# Cell_Balancing_Interface.net
KiCad netlist of a schematic drawn in Altium Designer
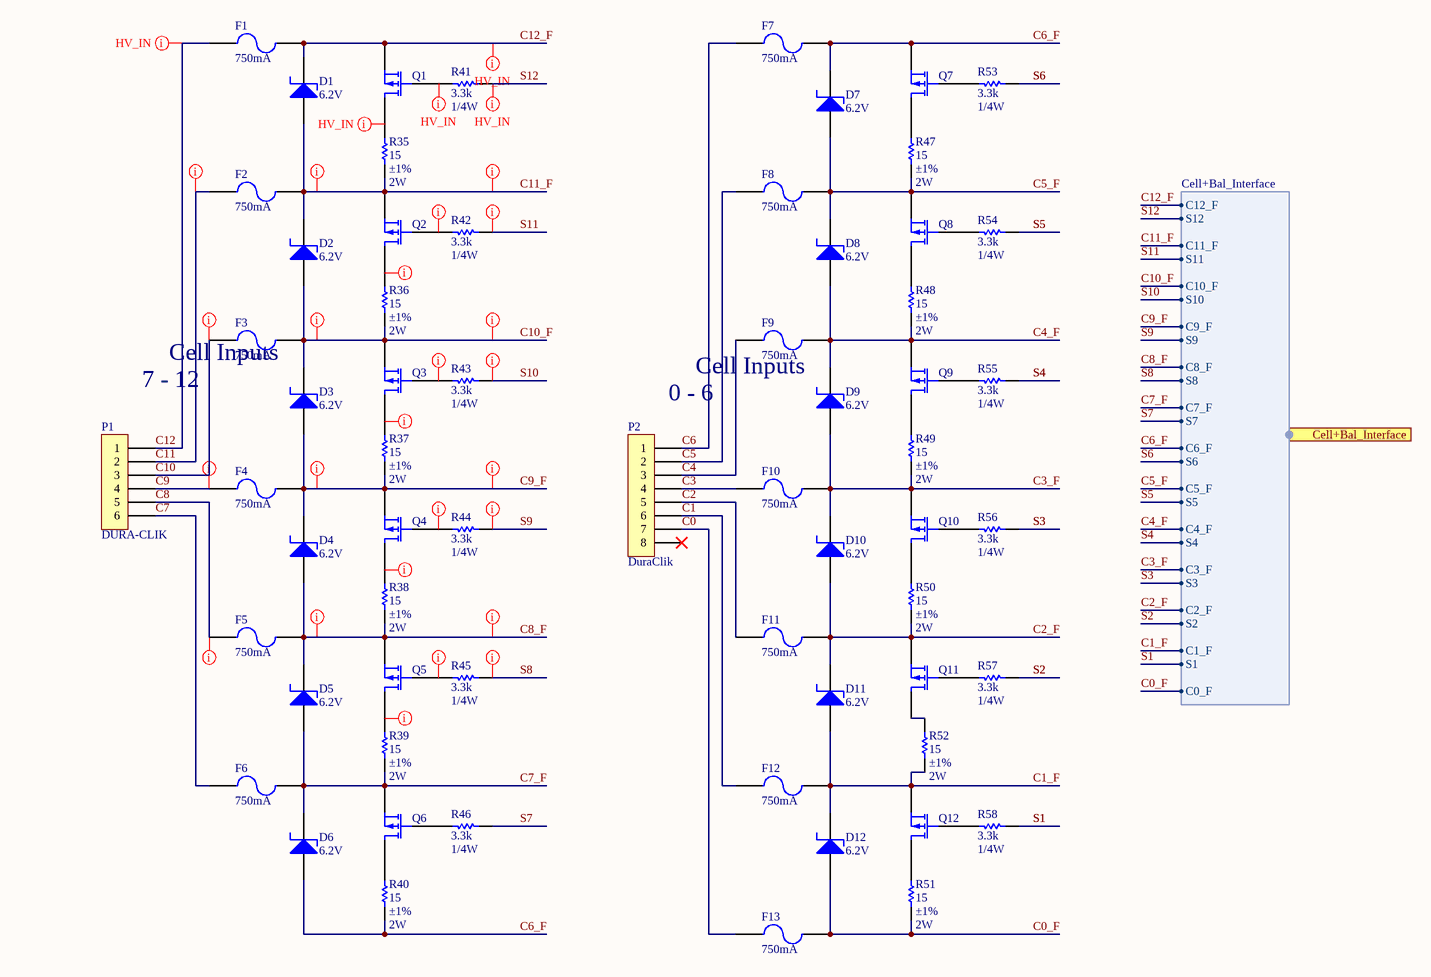
[diagram p0: Cell+Balancing_Interface.SchDoc]

(export (version "E")
  (design (tool "Eeschema 10.0.6"))
  (components
    (comp (ref "D1")
      (value "DIODE ZENER 6.2V 5W DO214AA")
      (footprint "DO-214AA Diode")
      (description "Zener Diode 6.2V 5W ±5% Surface Mount DO-214AA (SMB)")
      (fields (field (name "TOLERANCE") "±5%") (field (name "VOLTAGE - ZENER (NOM)") "6.2V"))
      (libsource (lib "Schematic Diagrams") (part "DIODE ZENER 6.2V 5W DO214AA"))
    )
    (comp (ref "D2")
      (value "DIODE ZENER 6.2V 5W DO214AA")
      (footprint "DO-214AA Diode")
      (description "Zener Diode 6.2V 5W ±5% Surface Mount DO-214AA (SMB)")
      (fields (field (name "TOLERANCE") "±5%") (field (name "VOLTAGE - ZENER (NOM)") "6.2V"))
      (libsource (lib "Schematic Diagrams") (part "DIODE ZENER 6.2V 5W DO214AA"))
    )
    (comp (ref "D3")
      (value "DIODE ZENER 6.2V 5W DO214AA")
      (footprint "DO-214AA Diode")
      (description "Zener Diode 6.2V 5W ±5% Surface Mount DO-214AA (SMB)")
      (fields (field (name "TOLERANCE") "±5%") (field (name "VOLTAGE - ZENER (NOM)") "6.2V"))
      (libsource (lib "Schematic Diagrams") (part "DIODE ZENER 6.2V 5W DO214AA"))
    )
    (comp (ref "D4")
      (value "DIODE ZENER 6.2V 5W DO214AA")
      (footprint "DO-214AA Diode")
      (description "Zener Diode 6.2V 5W ±5% Surface Mount DO-214AA (SMB)")
      (fields (field (name "TOLERANCE") "±5%") (field (name "VOLTAGE - ZENER (NOM)") "6.2V"))
      (libsource (lib "Schematic Diagrams") (part "DIODE ZENER 6.2V 5W DO214AA"))
    )
    (comp (ref "D5")
      (value "DIODE ZENER 6.2V 5W DO214AA")
      (footprint "DO-214AA Diode")
      (description "Zener Diode 6.2V 5W ±5% Surface Mount DO-214AA (SMB)")
      (fields (field (name "TOLERANCE") "±5%") (field (name "VOLTAGE - ZENER (NOM)") "6.2V"))
      (libsource (lib "Schematic Diagrams") (part "DIODE ZENER 6.2V 5W DO214AA"))
    )
    (comp (ref "D6")
      (value "DIODE ZENER 6.2V 5W DO214AA")
      (footprint "DO-214AA Diode")
      (description "Zener Diode 6.2V 5W ±5% Surface Mount DO-214AA (SMB)")
      (fields (field (name "TOLERANCE") "±5%") (field (name "VOLTAGE - ZENER (NOM)") "6.2V"))
      (libsource (lib "Schematic Diagrams") (part "DIODE ZENER 6.2V 5W DO214AA"))
    )
    (comp (ref "D7")
      (value "DIODE ZENER 6.2V 5W DO214AA")
      (footprint "DO-214AA Diode")
      (description "Zener Diode 6.2V 5W ±5% Surface Mount DO-214AA (SMB)")
      (fields (field (name "TOLERANCE") "±5%") (field (name "VOLTAGE - ZENER (NOM)") "6.2V"))
      (libsource (lib "Schematic Diagrams") (part "DIODE ZENER 6.2V 5W DO214AA"))
    )
    (comp (ref "D8")
      (value "DIODE ZENER 6.2V 5W DO214AA")
      (footprint "DO-214AA Diode")
      (description "Zener Diode 6.2V 5W ±5% Surface Mount DO-214AA (SMB)")
      (fields (field (name "TOLERANCE") "±5%") (field (name "VOLTAGE - ZENER (NOM)") "6.2V"))
      (libsource (lib "Schematic Diagrams") (part "DIODE ZENER 6.2V 5W DO214AA"))
    )
    (comp (ref "D9")
      (value "DIODE ZENER 6.2V 5W DO214AA")
      (footprint "DO-214AA Diode")
      (description "Zener Diode 6.2V 5W ±5% Surface Mount DO-214AA (SMB)")
      (fields (field (name "TOLERANCE") "±5%") (field (name "VOLTAGE - ZENER (NOM)") "6.2V"))
      (libsource (lib "Schematic Diagrams") (part "DIODE ZENER 6.2V 5W DO214AA"))
    )
    (comp (ref "D10")
      (value "DIODE ZENER 6.2V 5W DO214AA")
      (footprint "DO-214AA Diode")
      (description "Zener Diode 6.2V 5W ±5% Surface Mount DO-214AA (SMB)")
      (fields (field (name "TOLERANCE") "±5%") (field (name "VOLTAGE - ZENER (NOM)") "6.2V"))
      (libsource (lib "Schematic Diagrams") (part "DIODE ZENER 6.2V 5W DO214AA"))
    )
    (comp (ref "D11")
      (value "DIODE ZENER 6.2V 5W DO214AA")
      (footprint "DO-214AA Diode")
      (description "Zener Diode 6.2V 5W ±5% Surface Mount DO-214AA (SMB)")
      (fields (field (name "TOLERANCE") "±5%") (field (name "VOLTAGE - ZENER (NOM)") "6.2V"))
      (libsource (lib "Schematic Diagrams") (part "DIODE ZENER 6.2V 5W DO214AA"))
    )
    (comp (ref "D12")
      (value "DIODE ZENER 6.2V 5W DO214AA")
      (footprint "DO-214AA Diode")
      (description "Zener Diode 6.2V 5W ±5% Surface Mount DO-214AA (SMB)")
      (fields (field (name "TOLERANCE") "±5%") (field (name "VOLTAGE - ZENER (NOM)") "6.2V"))
      (libsource (lib "Schematic Diagrams") (part "DIODE ZENER 6.2V 5W DO214AA"))
    )
    (comp (ref "F1")
      (value "FUSE SMT 750MA")
      (footprint "RES, 0603")
      (description "Board Mount Fuse 750MA 32VAC 63VDC")
      (fields (field (name "CURRENT RATING") "750mA"))
      (libsource (lib "Schematic Diagrams") (part "FUSE SMT 750MA"))
    )
    (comp (ref "F2")
      (value "FUSE SMT 750MA")
      (footprint "RES, 0603")
      (description "Board Mount Fuse 750MA 32VAC 63VDC")
      (fields (field (name "CURRENT RATING") "750mA"))
      (libsource (lib "Schematic Diagrams") (part "FUSE SMT 750MA"))
    )
    (comp (ref "F3")
      (value "FUSE SMT 750MA")
      (footprint "RES, 0603")
      (description "Board Mount Fuse 750MA 32VAC 63VDC")
      (fields (field (name "CURRENT RATING") "750mA"))
      (libsource (lib "Schematic Diagrams") (part "FUSE SMT 750MA"))
    )
    (comp (ref "F4")
      (value "FUSE SMT 750MA")
      (footprint "RES, 0603")
      (description "Board Mount Fuse 750MA 32VAC 63VDC")
      (fields (field (name "CURRENT RATING") "750mA"))
      (libsource (lib "Schematic Diagrams") (part "FUSE SMT 750MA"))
    )
    (comp (ref "F5")
      (value "FUSE SMT 750MA")
      (footprint "RES, 0603")
      (description "Board Mount Fuse 750MA 32VAC 63VDC")
      (fields (field (name "CURRENT RATING") "750mA"))
      (libsource (lib "Schematic Diagrams") (part "FUSE SMT 750MA"))
    )
    (comp (ref "F6")
      (value "FUSE SMT 750MA")
      (footprint "RES, 0603")
      (description "Board Mount Fuse 750MA 32VAC 63VDC")
      (fields (field (name "CURRENT RATING") "750mA"))
      (libsource (lib "Schematic Diagrams") (part "FUSE SMT 750MA"))
    )
    (comp (ref "F7")
      (value "FUSE SMT 750MA")
      (footprint "RES, 0603")
      (description "Board Mount Fuse 750MA 32VAC 63VDC")
      (fields (field (name "CURRENT RATING") "750mA"))
      (libsource (lib "Schematic Diagrams") (part "FUSE SMT 750MA"))
    )
    (comp (ref "F8")
      (value "FUSE SMT 750MA")
      (footprint "RES, 0603")
      (description "Board Mount Fuse 750MA 32VAC 63VDC")
      (fields (field (name "CURRENT RATING") "750mA"))
      (libsource (lib "Schematic Diagrams") (part "FUSE SMT 750MA"))
    )
    (comp (ref "F9")
      (value "FUSE SMT 750MA")
      (footprint "RES, 0603")
      (description "Board Mount Fuse 750MA 32VAC 63VDC")
      (fields (field (name "CURRENT RATING") "750mA"))
      (libsource (lib "Schematic Diagrams") (part "FUSE SMT 750MA"))
    )
    (comp (ref "F10")
      (value "FUSE SMT 750MA")
      (footprint "RES, 0603")
      (description "Board Mount Fuse 750MA 32VAC 63VDC")
      (fields (field (name "CURRENT RATING") "750mA"))
      (libsource (lib "Schematic Diagrams") (part "FUSE SMT 750MA"))
    )
    (comp (ref "F11")
      (value "FUSE SMT 750MA")
      (footprint "RES, 0603")
      (description "Board Mount Fuse 750MA 32VAC 63VDC")
      (fields (field (name "CURRENT RATING") "750mA"))
      (libsource (lib "Schematic Diagrams") (part "FUSE SMT 750MA"))
    )
    (comp (ref "F12")
      (value "FUSE SMT 750MA")
      (footprint "RES, 0603")
      (description "Board Mount Fuse 750MA 32VAC 63VDC")
      (fields (field (name "CURRENT RATING") "750mA"))
      (libsource (lib "Schematic Diagrams") (part "FUSE SMT 750MA"))
    )
    (comp (ref "F13")
      (value "FUSE SMT 750MA")
      (footprint "RES, 0603")
      (description "Board Mount Fuse 750MA 32VAC 63VDC")
      (fields (field (name "CURRENT RATING") "750mA"))
      (libsource (lib "Schematic Diagrams") (part "FUSE SMT 750MA"))
    )
    (comp (ref "P1")
      (value "DURA-CLIK")
      (footprint "CONN, 6POS DURA-CLIK VERT")
      (description "6 Positions Header, Shrouded Connector 0.079\" (2.00mm) Surface Mount, Vertical Tin")
      (fields (field (name "MANUFACTURER") "Molex") (field (name "MANUFACTURER PART NUMBER") "5600200820"))
      (libsource (lib "Schematic Diagrams") (part "CONN 6POS DURA-CLIK 0.079{dblquote}"))
    )
    (comp (ref "P2")
      (value "CONN 8POS DURA-CLIK 0.079\"")
      (footprint "CONN, 8POS Dura-Clik")
      (description "8 Positions Header Connector 0.079\" (2.00mm) Surface Mount Tin")
      (fields (field (name "SERIES") "DuraClik"))
      (libsource (lib "Schematic Diagrams") (part "CONN 8POS DURA-CLIK 0.079{dblquote}"))
    )
    (comp (ref "Q1")
      (value "MOSFET P-CH 16V 2.5A X2-DFN2015")
      (footprint "DFN86P197X40-3N")
      (description "P-Channel 16V 2.5A (Ta) 650mW (Ta) Surface Mount X2-DFN2015-3")
      (libsource (lib "Schematic Diagrams") (part "MOSFET P-CH 16V 2.5A X2-DFN2015"))
    )
    (comp (ref "Q2")
      (value "MOSFET P-CH 16V 2.5A X2-DFN2015")
      (footprint "DFN86P197X40-3N")
      (description "P-Channel 16V 2.5A (Ta) 650mW (Ta) Surface Mount X2-DFN2015-3")
      (libsource (lib "Schematic Diagrams") (part "MOSFET P-CH 16V 2.5A X2-DFN2015"))
    )
    (comp (ref "Q3")
      (value "MOSFET P-CH 16V 2.5A X2-DFN2015")
      (footprint "DFN86P197X40-3N")
      (description "P-Channel 16V 2.5A (Ta) 650mW (Ta) Surface Mount X2-DFN2015-3")
      (libsource (lib "Schematic Diagrams") (part "MOSFET P-CH 16V 2.5A X2-DFN2015"))
    )
    (comp (ref "Q4")
      (value "MOSFET P-CH 16V 2.5A X2-DFN2015")
      (footprint "DFN86P197X40-3N")
      (description "P-Channel 16V 2.5A (Ta) 650mW (Ta) Surface Mount X2-DFN2015-3")
      (libsource (lib "Schematic Diagrams") (part "MOSFET P-CH 16V 2.5A X2-DFN2015"))
    )
    (comp (ref "Q5")
      (value "MOSFET P-CH 16V 2.5A X2-DFN2015")
      (footprint "DFN86P197X40-3N")
      (description "P-Channel 16V 2.5A (Ta) 650mW (Ta) Surface Mount X2-DFN2015-3")
      (libsource (lib "Schematic Diagrams") (part "MOSFET P-CH 16V 2.5A X2-DFN2015"))
    )
    (comp (ref "Q6")
      (value "MOSFET P-CH 16V 2.5A X2-DFN2015")
      (footprint "DFN86P197X40-3N")
      (description "P-Channel 16V 2.5A (Ta) 650mW (Ta) Surface Mount X2-DFN2015-3")
      (libsource (lib "Schematic Diagrams") (part "MOSFET P-CH 16V 2.5A X2-DFN2015"))
    )
    (comp (ref "Q7")
      (value "MOSFET P-CH 16V 2.5A X2-DFN2015")
      (footprint "DFN86P197X40-3N")
      (description "P-Channel 16V 2.5A (Ta) 650mW (Ta) Surface Mount X2-DFN2015-3")
      (libsource (lib "Schematic Diagrams") (part "MOSFET P-CH 16V 2.5A X2-DFN2015"))
    )
    (comp (ref "Q8")
      (value "MOSFET P-CH 16V 2.5A X2-DFN2015")
      (footprint "DFN86P197X40-3N")
      (description "P-Channel 16V 2.5A (Ta) 650mW (Ta) Surface Mount X2-DFN2015-3")
      (libsource (lib "Schematic Diagrams") (part "MOSFET P-CH 16V 2.5A X2-DFN2015"))
    )
    (comp (ref "Q9")
      (value "MOSFET P-CH 16V 2.5A X2-DFN2015")
      (footprint "DFN86P197X40-3N")
      (description "P-Channel 16V 2.5A (Ta) 650mW (Ta) Surface Mount X2-DFN2015-3")
      (libsource (lib "Schematic Diagrams") (part "MOSFET P-CH 16V 2.5A X2-DFN2015"))
    )
    (comp (ref "Q10")
      (value "MOSFET P-CH 16V 2.5A X2-DFN2015")
      (footprint "DFN86P197X40-3N")
      (description "P-Channel 16V 2.5A (Ta) 650mW (Ta) Surface Mount X2-DFN2015-3")
      (libsource (lib "Schematic Diagrams") (part "MOSFET P-CH 16V 2.5A X2-DFN2015"))
    )
    (comp (ref "Q11")
      (value "MOSFET P-CH 16V 2.5A X2-DFN2015")
      (footprint "DFN86P197X40-3N")
      (description "P-Channel 16V 2.5A (Ta) 650mW (Ta) Surface Mount X2-DFN2015-3")
      (libsource (lib "Schematic Diagrams") (part "MOSFET P-CH 16V 2.5A X2-DFN2015"))
    )
    (comp (ref "Q12")
      (value "MOSFET P-CH 16V 2.5A X2-DFN2015")
      (footprint "DFN86P197X40-3N")
      (description "P-Channel 16V 2.5A (Ta) 650mW (Ta) Surface Mount X2-DFN2015-3")
      (libsource (lib "Schematic Diagrams") (part "MOSFET P-CH 16V 2.5A X2-DFN2015"))
    )
    (comp (ref "R35")
      (value "RES 15 OHM 1% 2W 2512")
      (footprint "RES2512")
      (description "15 Ohm ±1% 2W Chip Resistor 2512 (6432 Metric) Thick Film")
      (fields (field (name "RESISTANCE") "15") (field (name "TOLERANCE") "±1%") (field (name "POWER") "2W"))
      (libsource (lib "Schematic Diagrams") (part "RES 15 OHM 1% 2W 2512"))
    )
    (comp (ref "R36")
      (value "RES 15 OHM 1% 2W 2512")
      (footprint "RES2512")
      (description "15 Ohm ±1% 2W Chip Resistor 2512 (6432 Metric) Thick Film")
      (fields (field (name "RESISTANCE") "15") (field (name "TOLERANCE") "±1%") (field (name "POWER") "2W"))
      (libsource (lib "Schematic Diagrams") (part "RES 15 OHM 1% 2W 2512"))
    )
    (comp (ref "R37")
      (value "RES 15 OHM 1% 2W 2512")
      (footprint "RES2512")
      (description "15 Ohm ±1% 2W Chip Resistor 2512 (6432 Metric) Thick Film")
      (fields (field (name "RESISTANCE") "15") (field (name "TOLERANCE") "±1%") (field (name "POWER") "2W"))
      (libsource (lib "Schematic Diagrams") (part "RES 15 OHM 1% 2W 2512"))
    )
    (comp (ref "R38")
      (value "RES 15 OHM 1% 2W 2512")
      (footprint "RES2512")
      (description "15 Ohm ±1% 2W Chip Resistor 2512 (6432 Metric) Thick Film")
      (fields (field (name "RESISTANCE") "15") (field (name "TOLERANCE") "±1%") (field (name "POWER") "2W"))
      (libsource (lib "Schematic Diagrams") (part "RES 15 OHM 1% 2W 2512"))
    )
    (comp (ref "R39")
      (value "RES 15 OHM 1% 2W 2512")
      (footprint "RES2512")
      (description "15 Ohm ±1% 2W Chip Resistor 2512 (6432 Metric) Thick Film")
      (fields (field (name "RESISTANCE") "15") (field (name "TOLERANCE") "±1%") (field (name "POWER") "2W"))
      (libsource (lib "Schematic Diagrams") (part "RES 15 OHM 1% 2W 2512"))
    )
    (comp (ref "R40")
      (value "RES 15 OHM 1% 2W 2512")
      (footprint "RES2512")
      (description "15 Ohm ±1% 2W Chip Resistor 2512 (6432 Metric) Thick Film")
      (fields (field (name "RESISTANCE") "15") (field (name "TOLERANCE") "±1%") (field (name "POWER") "2W"))
      (libsource (lib "Schematic Diagrams") (part "RES 15 OHM 1% 2W 2512"))
    )
    (comp (ref "R41")
      (value "RES 3.3K OHM 1% 1/4W 0603")
      (footprint "RES, 0603")
      (fields
        (field (name "TOLERANCE") "±1%")
        (field (name "RESISTANCE") "3.3k")
        (field (name "POWER") "1/4W")
      )
      (libsource (lib "Schematic Diagrams") (part "RES 3.3K OHM 1% 1/4W 0603"))
    )
    (comp (ref "R42")
      (value "RES 3.3K OHM 1% 1/4W 0603")
      (footprint "RES, 0603")
      (fields
        (field (name "TOLERANCE") "±1%")
        (field (name "RESISTANCE") "3.3k")
        (field (name "POWER") "1/4W")
      )
      (libsource (lib "Schematic Diagrams") (part "RES 3.3K OHM 1% 1/4W 0603"))
    )
    (comp (ref "R43")
      (value "RES 3.3K OHM 1% 1/4W 0603")
      (footprint "RES, 0603")
      (fields
        (field (name "TOLERANCE") "±1%")
        (field (name "RESISTANCE") "3.3k")
        (field (name "POWER") "1/4W")
      )
      (libsource (lib "Schematic Diagrams") (part "RES 3.3K OHM 1% 1/4W 0603"))
    )
    (comp (ref "R44")
      (value "RES 3.3K OHM 1% 1/4W 0603")
      (footprint "RES, 0603")
      (fields
        (field (name "TOLERANCE") "±1%")
        (field (name "RESISTANCE") "3.3k")
        (field (name "POWER") "1/4W")
      )
      (libsource (lib "Schematic Diagrams") (part "RES 3.3K OHM 1% 1/4W 0603"))
    )
    (comp (ref "R45")
      (value "RES 3.3K OHM 1% 1/4W 0603")
      (footprint "RES, 0603")
      (fields
        (field (name "TOLERANCE") "±1%")
        (field (name "RESISTANCE") "3.3k")
        (field (name "POWER") "1/4W")
      )
      (libsource (lib "Schematic Diagrams") (part "RES 3.3K OHM 1% 1/4W 0603"))
    )
    (comp (ref "R46")
      (value "RES 3.3K OHM 1% 1/4W 0603")
      (footprint "RES, 0603")
      (fields
        (field (name "TOLERANCE") "±1%")
        (field (name "RESISTANCE") "3.3k")
        (field (name "POWER") "1/4W")
      )
      (libsource (lib "Schematic Diagrams") (part "RES 3.3K OHM 1% 1/4W 0603"))
    )
    (comp (ref "R47")
      (value "RES 15 OHM 1% 2W 2512")
      (footprint "RES2512")
      (description "15 Ohm ±1% 2W Chip Resistor 2512 (6432 Metric) Thick Film")
      (fields (field (name "RESISTANCE") "15") (field (name "TOLERANCE") "±1%") (field (name "POWER") "2W"))
      (libsource (lib "Schematic Diagrams") (part "RES 15 OHM 1% 2W 2512"))
    )
    (comp (ref "R48")
      (value "RES 15 OHM 1% 2W 2512")
      (footprint "RES2512")
      (description "15 Ohm ±1% 2W Chip Resistor 2512 (6432 Metric) Thick Film")
      (fields (field (name "RESISTANCE") "15") (field (name "TOLERANCE") "±1%") (field (name "POWER") "2W"))
      (libsource (lib "Schematic Diagrams") (part "RES 15 OHM 1% 2W 2512"))
    )
    (comp (ref "R49")
      (value "RES 15 OHM 1% 2W 2512")
      (footprint "RES2512")
      (description "15 Ohm ±1% 2W Chip Resistor 2512 (6432 Metric) Thick Film")
      (fields (field (name "RESISTANCE") "15") (field (name "TOLERANCE") "±1%") (field (name "POWER") "2W"))
      (libsource (lib "Schematic Diagrams") (part "RES 15 OHM 1% 2W 2512"))
    )
    (comp (ref "R50")
      (value "RES 15 OHM 1% 2W 2512")
      (footprint "RES2512")
      (description "15 Ohm ±1% 2W Chip Resistor 2512 (6432 Metric) Thick Film")
      (fields (field (name "RESISTANCE") "15") (field (name "TOLERANCE") "±1%") (field (name "POWER") "2W"))
      (libsource (lib "Schematic Diagrams") (part "RES 15 OHM 1% 2W 2512"))
    )
    (comp (ref "R51")
      (value "RES 15 OHM 1% 2W 2512")
      (footprint "RES2512")
      (description "15 Ohm ±1% 2W Chip Resistor 2512 (6432 Metric) Thick Film")
      (fields (field (name "RESISTANCE") "15") (field (name "TOLERANCE") "±1%") (field (name "POWER") "2W"))
      (libsource (lib "Schematic Diagrams") (part "RES 15 OHM 1% 2W 2512"))
    )
    (comp (ref "R52")
      (value "RES 15 OHM 1% 2W 2512")
      (footprint "RES2512")
      (description "15 Ohm ±1% 2W Chip Resistor 2512 (6432 Metric) Thick Film")
      (fields (field (name "RESISTANCE") "15") (field (name "TOLERANCE") "±1%") (field (name "POWER") "2W"))
      (libsource (lib "Schematic Diagrams") (part "RES 15 OHM 1% 2W 2512"))
    )
    (comp (ref "R53")
      (value "RES 3.3K OHM 1% 1/4W 0603")
      (footprint "RES, 0603")
      (fields
        (field (name "TOLERANCE") "±1%")
        (field (name "RESISTANCE") "3.3k")
        (field (name "POWER") "1/4W")
      )
      (libsource (lib "Schematic Diagrams") (part "RES 3.3K OHM 1% 1/4W 0603"))
    )
    (comp (ref "R54")
      (value "RES 3.3K OHM 1% 1/4W 0603")
      (footprint "RES, 0603")
      (fields
        (field (name "TOLERANCE") "±1%")
        (field (name "RESISTANCE") "3.3k")
        (field (name "POWER") "1/4W")
      )
      (libsource (lib "Schematic Diagrams") (part "RES 3.3K OHM 1% 1/4W 0603"))
    )
    (comp (ref "R55")
      (value "RES 3.3K OHM 1% 1/4W 0603")
      (footprint "RES, 0603")
      (fields
        (field (name "TOLERANCE") "±1%")
        (field (name "RESISTANCE") "3.3k")
        (field (name "POWER") "1/4W")
      )
      (libsource (lib "Schematic Diagrams") (part "RES 3.3K OHM 1% 1/4W 0603"))
    )
    (comp (ref "R56")
      (value "RES 3.3K OHM 1% 1/4W 0603")
      (footprint "RES, 0603")
      (fields
        (field (name "TOLERANCE") "±1%")
        (field (name "RESISTANCE") "3.3k")
        (field (name "POWER") "1/4W")
      )
      (libsource (lib "Schematic Diagrams") (part "RES 3.3K OHM 1% 1/4W 0603"))
    )
    (comp (ref "R57")
      (value "RES 3.3K OHM 1% 1/4W 0603")
      (footprint "RES, 0603")
      (fields
        (field (name "TOLERANCE") "±1%")
        (field (name "RESISTANCE") "3.3k")
        (field (name "POWER") "1/4W")
      )
      (libsource (lib "Schematic Diagrams") (part "RES 3.3K OHM 1% 1/4W 0603"))
    )
    (comp (ref "R58")
      (value "RES 3.3K OHM 1% 1/4W 0603")
      (footprint "RES, 0603")
      (fields
        (field (name "TOLERANCE") "±1%")
        (field (name "RESISTANCE") "3.3k")
        (field (name "POWER") "1/4W")
      )
      (libsource (lib "Schematic Diagrams") (part "RES 3.3K OHM 1% 1/4W 0603"))
    )
  )
  (nets
    (net (code "2") (name "/C0") (class "Default")
      (node (ref "F13") (pin "1") (pinfunction "1_1") (pintype "passive"))
      (node (ref "P2") (pin "7") (pinfunction "7_7") (pintype "passive"))
    )
    (net (code "3") (name "/C0_F") (class "Default")
      (node (ref "D12") (pin "1") (pinfunction "A_1") (pintype "passive"))
      (node (ref "F13") (pin "2") (pinfunction "2_2") (pintype "passive"))
      (node (ref "R51") (pin "1") (pinfunction "1_1") (pintype "passive"))
    )
    (net (code "4") (name "/C1") (class "Default")
      (node (ref "F12") (pin "1") (pinfunction "1_1") (pintype "passive"))
      (node (ref "P2") (pin "6") (pinfunction "6_6") (pintype "passive"))
    )
    (net (code "5") (name "/C1_F") (class "Default")
      (node (ref "D11") (pin "1") (pinfunction "A_1") (pintype "passive"))
      (node (ref "D12") (pin "2") (pinfunction "K_2") (pintype "passive"))
      (node (ref "F12") (pin "2") (pinfunction "2_2") (pintype "passive"))
      (node (ref "Q12") (pin "2") (pinfunction "S_2") (pintype "passive"))
      (node (ref "R52") (pin "1") (pinfunction "1_1") (pintype "passive"))
    )
    (net (code "6") (name "/C2") (class "Default")
      (node (ref "F11") (pin "1") (pinfunction "1_1") (pintype "passive"))
      (node (ref "P2") (pin "5") (pinfunction "5_5") (pintype "passive"))
    )
    (net (code "7") (name "/C2_F") (class "Default")
      (node (ref "D10") (pin "1") (pinfunction "A_1") (pintype "passive"))
      (node (ref "D11") (pin "2") (pinfunction "K_2") (pintype "passive"))
      (node (ref "F11") (pin "2") (pinfunction "2_2") (pintype "passive"))
      (node (ref "Q11") (pin "2") (pinfunction "S_2") (pintype "passive"))
      (node (ref "R50") (pin "1") (pinfunction "1_1") (pintype "passive"))
    )
    (net (code "8") (name "/C3") (class "Default")
      (node (ref "F10") (pin "1") (pinfunction "1_1") (pintype "passive"))
      (node (ref "P2") (pin "4") (pinfunction "4_4") (pintype "passive"))
    )
    (net (code "9") (name "/C3_F") (class "Default")
      (node (ref "D10") (pin "2") (pinfunction "K_2") (pintype "passive"))
      (node (ref "D9") (pin "1") (pinfunction "A_1") (pintype "passive"))
      (node (ref "F10") (pin "2") (pinfunction "2_2") (pintype "passive"))
      (node (ref "Q10") (pin "2") (pinfunction "S_2") (pintype "passive"))
      (node (ref "R49") (pin "1") (pinfunction "1_1") (pintype "passive"))
    )
    (net (code "10") (name "/C4") (class "Default")
      (node (ref "F9") (pin "1") (pinfunction "1_1") (pintype "passive"))
      (node (ref "P2") (pin "3") (pinfunction "3_3") (pintype "passive"))
    )
    (net (code "11") (name "/C4_F") (class "Default")
      (node (ref "D8") (pin "1") (pinfunction "A_1") (pintype "passive"))
      (node (ref "D9") (pin "2") (pinfunction "K_2") (pintype "passive"))
      (node (ref "F9") (pin "2") (pinfunction "2_2") (pintype "passive"))
      (node (ref "Q9") (pin "2") (pinfunction "S_2") (pintype "passive"))
      (node (ref "R48") (pin "1") (pinfunction "1_1") (pintype "passive"))
    )
    (net (code "12") (name "/C5") (class "Default")
      (node (ref "F8") (pin "1") (pinfunction "1_1") (pintype "passive"))
      (node (ref "P2") (pin "2") (pinfunction "2_2") (pintype "passive"))
    )
    (net (code "13") (name "/C5_F") (class "Default")
      (node (ref "D7") (pin "1") (pinfunction "A_1") (pintype "passive"))
      (node (ref "D8") (pin "2") (pinfunction "K_2") (pintype "passive"))
      (node (ref "F8") (pin "2") (pinfunction "2_2") (pintype "passive"))
      (node (ref "Q8") (pin "2") (pinfunction "S_2") (pintype "passive"))
      (node (ref "R47") (pin "1") (pinfunction "1_1") (pintype "passive"))
    )
    (net (code "14") (name "/C6") (class "Default")
      (node (ref "F7") (pin "1") (pinfunction "1_1") (pintype "passive"))
      (node (ref "P2") (pin "1") (pinfunction "1_1") (pintype "passive"))
    )
    (net (code "15") (name "/C6_F") (class "Default")
      (node (ref "D6") (pin "1") (pinfunction "A_1") (pintype "passive"))
      (node (ref "D7") (pin "2") (pinfunction "K_2") (pintype "passive"))
      (node (ref "F7") (pin "2") (pinfunction "2_2") (pintype "passive"))
      (node (ref "Q7") (pin "2") (pinfunction "S_2") (pintype "passive"))
      (node (ref "R40") (pin "1") (pinfunction "1_1") (pintype "passive"))
    )
    (net (code "16") (name "/C7") (class "Default")
      (node (ref "F6") (pin "1") (pinfunction "1_1") (pintype "passive"))
      (node (ref "P1") (pin "6") (pinfunction "6_6") (pintype "passive"))
    )
    (net (code "17") (name "/C7_F") (class "Default")
      (node (ref "D5") (pin "1") (pinfunction "A_1") (pintype "passive"))
      (node (ref "D6") (pin "2") (pinfunction "K_2") (pintype "passive"))
      (node (ref "F6") (pin "2") (pinfunction "2_2") (pintype "passive"))
      (node (ref "Q6") (pin "2") (pinfunction "S_2") (pintype "passive"))
      (node (ref "R39") (pin "1") (pinfunction "1_1") (pintype "passive"))
    )
    (net (code "18") (name "/C8") (class "Default")
      (node (ref "F5") (pin "1") (pinfunction "1_1") (pintype "passive"))
      (node (ref "P1") (pin "5") (pinfunction "5_5") (pintype "passive"))
    )
    (net (code "19") (name "/C8_F") (class "Default")
      (node (ref "D4") (pin "1") (pinfunction "A_1") (pintype "passive"))
      (node (ref "D5") (pin "2") (pinfunction "K_2") (pintype "passive"))
      (node (ref "F5") (pin "2") (pinfunction "2_2") (pintype "passive"))
      (node (ref "Q5") (pin "2") (pinfunction "S_2") (pintype "passive"))
      (node (ref "R38") (pin "1") (pinfunction "1_1") (pintype "passive"))
    )
    (net (code "20") (name "/C9") (class "Default")
      (node (ref "F4") (pin "1") (pinfunction "1_1") (pintype "passive"))
      (node (ref "P1") (pin "4") (pinfunction "4_4") (pintype "passive"))
    )
    (net (code "21") (name "/C9_F") (class "Default")
      (node (ref "D3") (pin "1") (pinfunction "A_1") (pintype "passive"))
      (node (ref "D4") (pin "2") (pinfunction "K_2") (pintype "passive"))
      (node (ref "F4") (pin "2") (pinfunction "2_2") (pintype "passive"))
      (node (ref "Q4") (pin "2") (pinfunction "S_2") (pintype "passive"))
      (node (ref "R37") (pin "1") (pinfunction "1_1") (pintype "passive"))
    )
    (net (code "22") (name "/C10") (class "Default")
      (node (ref "F3") (pin "1") (pinfunction "1_1") (pintype "passive"))
      (node (ref "P1") (pin "3") (pinfunction "3_3") (pintype "passive"))
    )
    (net (code "23") (name "/C10_F") (class "Default")
      (node (ref "D2") (pin "1") (pinfunction "A_1") (pintype "passive"))
      (node (ref "D3") (pin "2") (pinfunction "K_2") (pintype "passive"))
      (node (ref "F3") (pin "2") (pinfunction "2_2") (pintype "passive"))
      (node (ref "Q3") (pin "2") (pinfunction "S_2") (pintype "passive"))
      (node (ref "R36") (pin "1") (pinfunction "1_1") (pintype "passive"))
    )
    (net (code "24") (name "/C11") (class "Default")
      (node (ref "F2") (pin "1") (pinfunction "1_1") (pintype "passive"))
      (node (ref "P1") (pin "2") (pinfunction "2_2") (pintype "passive"))
    )
    (net (code "25") (name "/C11_F") (class "Default")
      (node (ref "D1") (pin "1") (pinfunction "A_1") (pintype "passive"))
      (node (ref "D2") (pin "2") (pinfunction "K_2") (pintype "passive"))
      (node (ref "F2") (pin "2") (pinfunction "2_2") (pintype "passive"))
      (node (ref "Q2") (pin "2") (pinfunction "S_2") (pintype "passive"))
      (node (ref "R35") (pin "1") (pinfunction "1_1") (pintype "passive"))
    )
    (net (code "26") (name "/C12") (class "Default")
      (node (ref "F1") (pin "1") (pinfunction "1_1") (pintype "passive"))
      (node (ref "P1") (pin "1") (pinfunction "1_1") (pintype "passive"))
    )
    (net (code "27") (name "/C12_F") (class "Default")
      (node (ref "D1") (pin "2") (pinfunction "K_2") (pintype "passive"))
      (node (ref "F1") (pin "2") (pinfunction "2_2") (pintype "passive"))
      (node (ref "Q1") (pin "2") (pinfunction "S_2") (pintype "passive"))
    )
    (net (code "28") (name "/S1") (class "Default")
      (node (ref "R58") (pin "1") (pinfunction "1_1") (pintype "passive"))
    )
    (net (code "29") (name "/S2") (class "Default")
      (node (ref "R57") (pin "1") (pinfunction "1_1") (pintype "passive"))
    )
    (net (code "30") (name "/S3") (class "Default")
      (node (ref "R56") (pin "1") (pinfunction "1_1") (pintype "passive"))
    )
    (net (code "31") (name "/S4") (class "Default")
      (node (ref "R55") (pin "1") (pinfunction "1_1") (pintype "passive"))
    )
    (net (code "32") (name "/S5") (class "Default")
      (node (ref "R54") (pin "1") (pinfunction "1_1") (pintype "passive"))
    )
    (net (code "33") (name "/S6") (class "Default")
      (node (ref "R53") (pin "1") (pinfunction "1_1") (pintype "passive"))
    )
    (net (code "34") (name "/S7") (class "Default")
      (node (ref "R46") (pin "1") (pinfunction "1_1") (pintype "passive"))
    )
    (net (code "35") (name "/S8") (class "Default")
      (node (ref "R45") (pin "1") (pinfunction "1_1") (pintype "passive"))
    )
    (net (code "36") (name "/S9") (class "Default")
      (node (ref "R44") (pin "1") (pinfunction "1_1") (pintype "passive"))
    )
    (net (code "37") (name "/S10") (class "Default")
      (node (ref "R43") (pin "1") (pinfunction "1_1") (pintype "passive"))
    )
    (net (code "38") (name "/S11") (class "Default")
      (node (ref "R42") (pin "1") (pinfunction "1_1") (pintype "passive"))
    )
    (net (code "39") (name "/S12") (class "Default")
      (node (ref "R41") (pin "1") (pinfunction "1_1") (pintype "passive"))
    )
    (net (code "41") (name "Net-(Q1-D)") (class "Default")
      (node (ref "Q1") (pin "3") (pinfunction "D_3") (pintype "passive"))
      (node (ref "R35") (pin "2") (pinfunction "2_2") (pintype "passive"))
    )
    (net (code "42") (name "Net-(Q1-G)") (class "Default")
      (node (ref "Q1") (pin "1") (pinfunction "G_1") (pintype "passive"))
      (node (ref "R41") (pin "2") (pinfunction "2_2") (pintype "passive"))
    )
    (net (code "43") (name "Net-(Q2-D)") (class "Default")
      (node (ref "Q2") (pin "3") (pinfunction "D_3") (pintype "passive"))
      (node (ref "R36") (pin "2") (pinfunction "2_2") (pintype "passive"))
    )
    (net (code "44") (name "Net-(Q2-G)") (class "Default")
      (node (ref "Q2") (pin "1") (pinfunction "G_1") (pintype "passive"))
      (node (ref "R42") (pin "2") (pinfunction "2_2") (pintype "passive"))
    )
    (net (code "45") (name "Net-(Q3-D)") (class "Default")
      (node (ref "Q3") (pin "3") (pinfunction "D_3") (pintype "passive"))
      (node (ref "R37") (pin "2") (pinfunction "2_2") (pintype "passive"))
    )
    (net (code "46") (name "Net-(Q3-G)") (class "Default")
      (node (ref "Q3") (pin "1") (pinfunction "G_1") (pintype "passive"))
      (node (ref "R43") (pin "2") (pinfunction "2_2") (pintype "passive"))
    )
    (net (code "47") (name "Net-(Q4-D)") (class "Default")
      (node (ref "Q4") (pin "3") (pinfunction "D_3") (pintype "passive"))
      (node (ref "R38") (pin "2") (pinfunction "2_2") (pintype "passive"))
    )
    (net (code "48") (name "Net-(Q4-G)") (class "Default")
      (node (ref "Q4") (pin "1") (pinfunction "G_1") (pintype "passive"))
      (node (ref "R44") (pin "2") (pinfunction "2_2") (pintype "passive"))
    )
    (net (code "49") (name "Net-(Q5-D)") (class "Default")
      (node (ref "Q5") (pin "3") (pinfunction "D_3") (pintype "passive"))
      (node (ref "R39") (pin "2") (pinfunction "2_2") (pintype "passive"))
    )
    (net (code "50") (name "Net-(Q5-G)") (class "Default")
      (node (ref "Q5") (pin "1") (pinfunction "G_1") (pintype "passive"))
      (node (ref "R45") (pin "2") (pinfunction "2_2") (pintype "passive"))
    )
    (net (code "51") (name "Net-(Q6-D)") (class "Default")
      (node (ref "Q6") (pin "3") (pinfunction "D_3") (pintype "passive"))
      (node (ref "R40") (pin "2") (pinfunction "2_2") (pintype "passive"))
    )
    (net (code "52") (name "Net-(Q6-G)") (class "Default")
      (node (ref "Q6") (pin "1") (pinfunction "G_1") (pintype "passive"))
      (node (ref "R46") (pin "2") (pinfunction "2_2") (pintype "passive"))
    )
    (net (code "53") (name "Net-(Q7-D)") (class "Default")
      (node (ref "Q7") (pin "3") (pinfunction "D_3") (pintype "passive"))
      (node (ref "R47") (pin "2") (pinfunction "2_2") (pintype "passive"))
    )
    (net (code "54") (name "Net-(Q7-G)") (class "Default")
      (node (ref "Q7") (pin "1") (pinfunction "G_1") (pintype "passive"))
      (node (ref "R53") (pin "2") (pinfunction "2_2") (pintype "passive"))
    )
    (net (code "55") (name "Net-(Q8-D)") (class "Default")
      (node (ref "Q8") (pin "3") (pinfunction "D_3") (pintype "passive"))
      (node (ref "R48") (pin "2") (pinfunction "2_2") (pintype "passive"))
    )
    (net (code "56") (name "Net-(Q8-G)") (class "Default")
      (node (ref "Q8") (pin "1") (pinfunction "G_1") (pintype "passive"))
      (node (ref "R54") (pin "2") (pinfunction "2_2") (pintype "passive"))
    )
    (net (code "57") (name "Net-(Q9-D)") (class "Default")
      (node (ref "Q9") (pin "3") (pinfunction "D_3") (pintype "passive"))
      (node (ref "R49") (pin "2") (pinfunction "2_2") (pintype "passive"))
    )
    (net (code "58") (name "Net-(Q9-G)") (class "Default")
      (node (ref "Q9") (pin "1") (pinfunction "G_1") (pintype "passive"))
      (node (ref "R55") (pin "2") (pinfunction "2_2") (pintype "passive"))
    )
    (net (code "59") (name "Net-(Q10-D)") (class "Default")
      (node (ref "Q10") (pin "3") (pinfunction "D_3") (pintype "passive"))
      (node (ref "R50") (pin "2") (pinfunction "2_2") (pintype "passive"))
    )
    (net (code "60") (name "Net-(Q10-G)") (class "Default")
      (node (ref "Q10") (pin "1") (pinfunction "G_1") (pintype "passive"))
      (node (ref "R56") (pin "2") (pinfunction "2_2") (pintype "passive"))
    )
    (net (code "61") (name "Net-(Q11-D)") (class "Default")
      (node (ref "Q11") (pin "3") (pinfunction "D_3") (pintype "passive"))
      (node (ref "R52") (pin "2") (pinfunction "2_2") (pintype "passive"))
    )
    (net (code "62") (name "Net-(Q11-G)") (class "Default")
      (node (ref "Q11") (pin "1") (pinfunction "G_1") (pintype "passive"))
      (node (ref "R57") (pin "2") (pinfunction "2_2") (pintype "passive"))
    )
    (net (code "63") (name "Net-(Q12-D)") (class "Default")
      (node (ref "Q12") (pin "3") (pinfunction "D_3") (pintype "passive"))
      (node (ref "R51") (pin "2") (pinfunction "2_2") (pintype "passive"))
    )
    (net (code "64") (name "Net-(Q12-G)") (class "Default")
      (node (ref "Q12") (pin "1") (pinfunction "G_1") (pintype "passive"))
      (node (ref "R58") (pin "2") (pinfunction "2_2") (pintype "passive"))
    )
    (net (code "65") (name "unconnected-(P2-Pad8)") (class "Default")
      (node (ref "P2") (pin "8") (pinfunction "8_8") (pintype "passive+no_connect"))
    )
  )
)
